# v1.net
KiCad netlist of a schematic drawn in Altium Designer
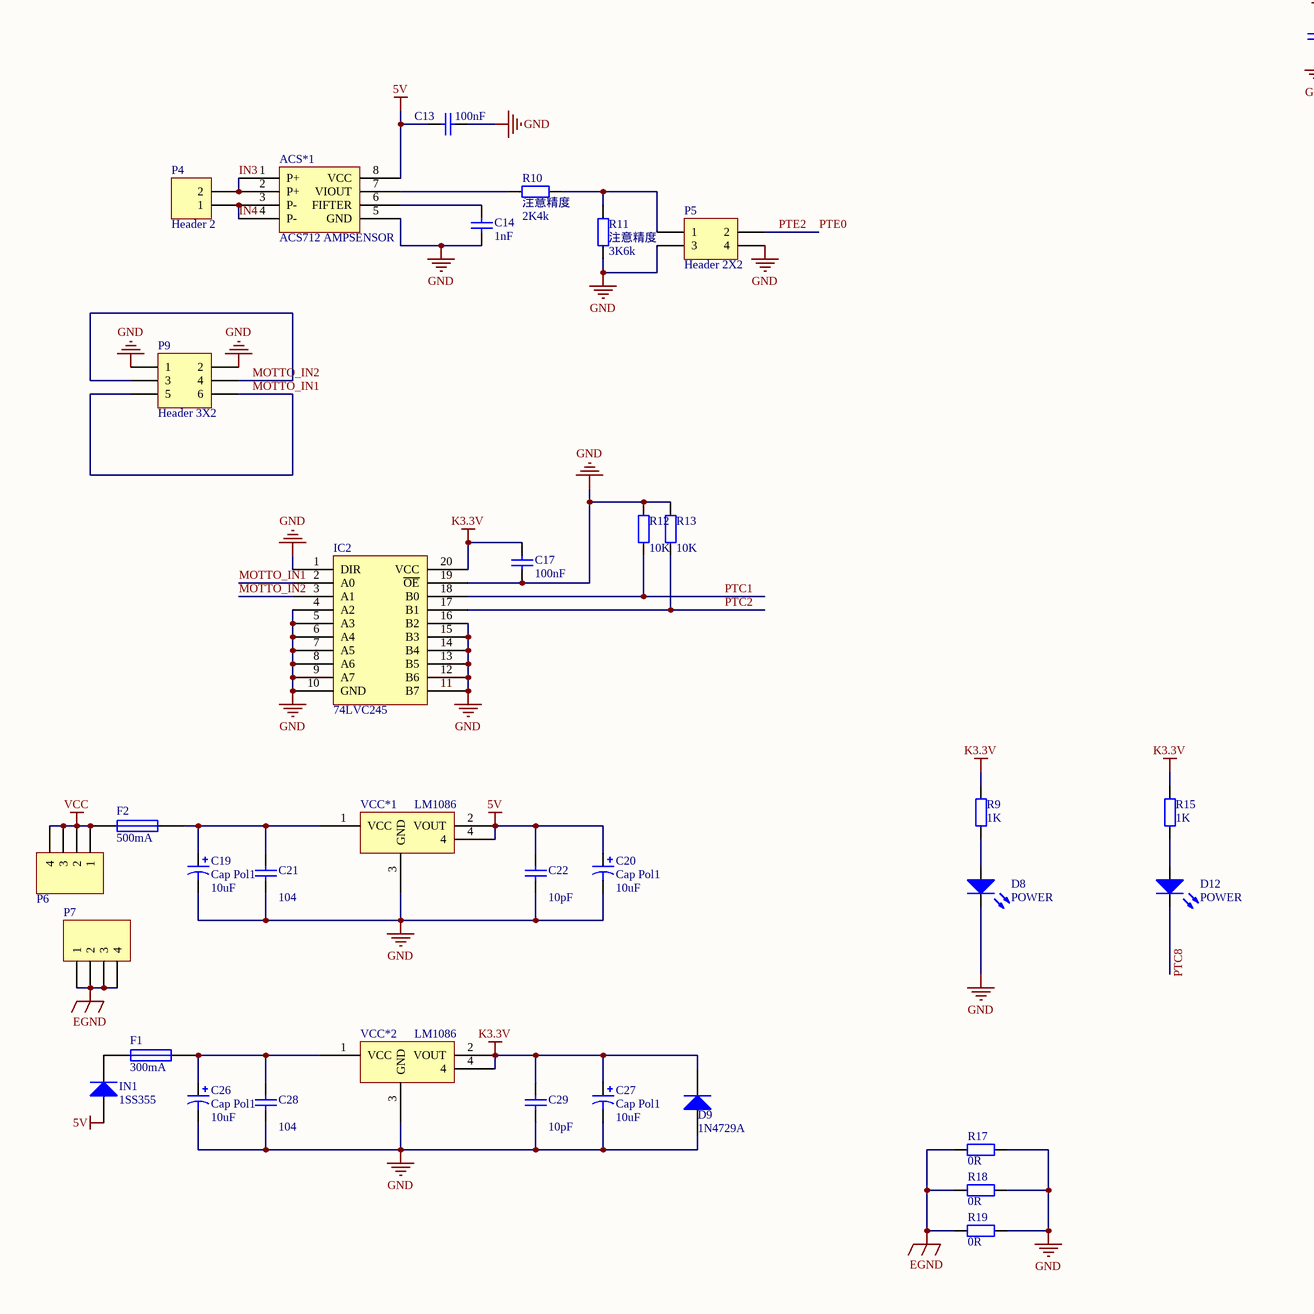
[diagram p0: 主控板加电流检测v1.SchDoc, left]
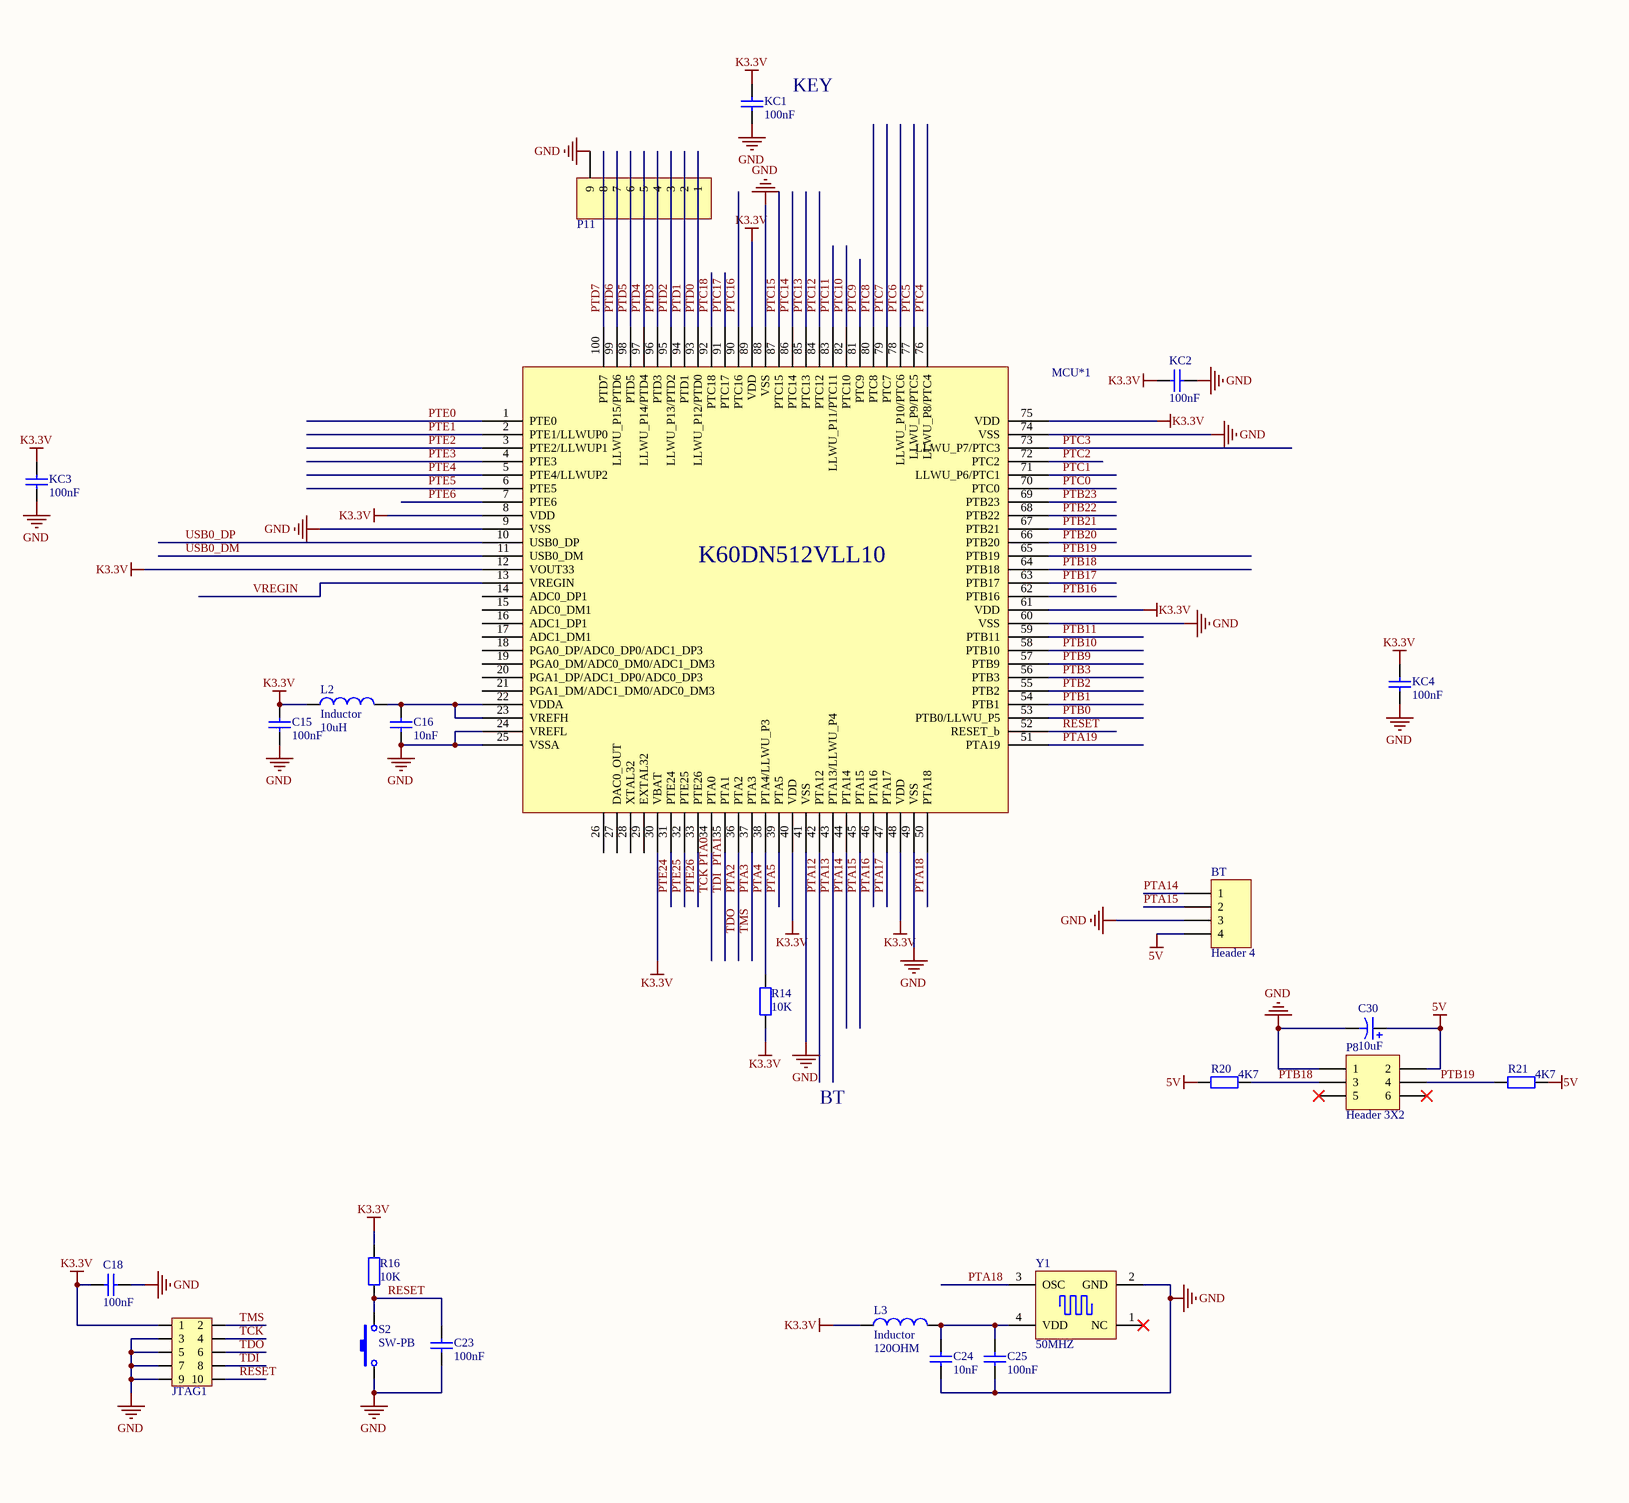
[diagram p1: 主控板加电流检测v1.SchDoc, right]

(export (version "E")
  (design (tool "Eeschema 10.0.6"))
  (components
    (comp (ref "ACS*1")
      (value "ACS712 AMPSENSOR")
      (footprint "SOIC1-8N ACS712")
      (libsource (lib "原理图") (part "ACS712 AMPSENSOR"))
    )
    (comp (ref "BT")
      (value "Header 4")
      (footprint "HDR1X4")
      (description "Header, 4-Pin")
      (fields (field (name "PUBLISHER") "Altium Limited"))
      (libsource (lib "") (part "Header 4_2"))
    )
    (comp (ref "C13")
      (value "100nF")
      (footprint "C2012")
      (description "Capacitor")
      (fields (field (name "Comment") "Cap") (field (name "PUBLISHER") "Altium Limited"))
      (libsource (lib "Miscellaneous Devices") (part "Cap"))
    )
    (comp (ref "C14")
      (value "1nF")
      (footprint "C2012")
      (description "Capacitor")
      (fields (field (name "Comment") "Cap") (field (name "PUBLISHER") "Altium Limited"))
      (libsource (lib "Miscellaneous Devices") (part "Cap"))
    )
    (comp (ref "C15")
      (value "100nF")
      (footprint "C2012")
      (description "Capacitor")
      (libsource (lib "K60-V4.0") (part "Cap"))
    )
    (comp (ref "C16")
      (value "10nF")
      (footprint "C2012")
      (description "Capacitor")
      (libsource (lib "K60-V4.0") (part "Cap"))
    )
    (comp (ref "C17")
      (value "100nF")
      (footprint "C2012")
      (description "Capacitor")
      (libsource (lib "Landzo") (part "Cap"))
    )
    (comp (ref "C18")
      (value "100nF")
      (footprint "C2012")
      (description "Capacitor")
      (libsource (lib "K60-V4.0") (part "Cap"))
    )
    (comp (ref "C19")
      (value "Cap Pol1")
      (footprint "1206(2)")
      (description "Polarized Capacitor (Radial)")
      (fields (field (name "ALTIUM_VALUE") "10uF") (field (name "PUBLISHER") "Altium Limited"))
      (libsource (lib "Miscellaneous Devices") (part "Cap Pol1"))
    )
    (comp (ref "C20")
      (value "Cap Pol1")
      (footprint "1206(2)")
      (description "Polarized Capacitor (Radial)")
      (fields (field (name "ALTIUM_VALUE") "10uF") (field (name "PUBLISHER") "Altium Limited"))
      (libsource (lib "Miscellaneous Devices") (part "Cap Pol1"))
    )
    (comp (ref "C21")
      (value "104")
      (footprint "C2012")
      (description "贴片电容")
      (fields (field (name "Comment") "Cap") (field (name "PUBLISHER") "Altium Limited"))
      (libsource (lib "Sparks") (part "Cap"))
    )
    (comp (ref "C22")
      (value "10pF")
      (footprint "C2012")
      (description "贴片电容")
      (fields (field (name "Comment") "Cap") (field (name "PUBLISHER") "Altium Limited"))
      (libsource (lib "Sparks") (part "Cap"))
    )
    (comp (ref "C23")
      (value "100nF")
      (footprint "C2012")
      (description "Capacitor")
      (libsource (lib "K60-V4.0") (part "Cap"))
    )
    (comp (ref "C24")
      (value "10nF")
      (footprint "C2012")
      (description "Capacitor")
      (libsource (lib "K60-V4.0") (part "Cap"))
    )
    (comp (ref "C25")
      (value "100nF")
      (footprint "C2012")
      (description "Capacitor")
      (libsource (lib "K60-V4.0") (part "Cap"))
    )
    (comp (ref "C26")
      (value "Cap Pol1")
      (footprint "1206(2)")
      (description "Polarized Capacitor (Radial)")
      (fields (field (name "ALTIUM_VALUE") "10uF") (field (name "PUBLISHER") "Altium Limited"))
      (libsource (lib "Miscellaneous Devices") (part "Cap Pol1"))
    )
    (comp (ref "C27")
      (value "Cap Pol1")
      (footprint "1206(2)")
      (description "Polarized Capacitor (Radial)")
      (fields (field (name "ALTIUM_VALUE") "10uF") (field (name "PUBLISHER") "Altium Limited"))
      (libsource (lib "Miscellaneous Devices") (part "Cap Pol1"))
    )
    (comp (ref "C28")
      (value "104")
      (footprint "C2012")
      (description "贴片电容")
      (fields (field (name "Comment") "Cap") (field (name "PUBLISHER") "Altium Limited"))
      (libsource (lib "Sparks") (part "Cap"))
    )
    (comp (ref "C29")
      (value "10pF")
      (footprint "C2012")
      (description "贴片电容")
      (fields (field (name "Comment") "Cap") (field (name "PUBLISHER") "Altium Limited"))
      (libsource (lib "Sparks") (part "Cap"))
    )
    (comp (ref "C30")
      (value "10uF")
      (footprint "c2012")
      (description "Polarized Capacitor (Radial)")
      (fields (field (name "Comment") "Cap Pol1") (field (name "PUBLISHER") "Altium Limited"))
      (libsource (lib "Miscellaneous Devices") (part "Cap Pol1"))
    )
    (comp (ref "D8")
      (value "POWER")
      (footprint "C2012")
      (description "Typical INFRARED GaAs LED")
      (libsource (lib "K60-V4.0") (part "LED"))
    )
    (comp (ref "D9")
      (value "1N4729A")
      (footprint "hole-chip diode")
      (description "High Conductance Fast Diode")
      (fields (field (name "PUBLISHER") "Altium Limited"))
      (libsource (lib "K60-V4.0") (part "Diode 1N4148"))
    )
    (comp (ref "D12")
      (value "POWER")
      (footprint "C2012")
      (description "Typical INFRARED GaAs LED")
      (libsource (lib "K60-V4.0") (part "LED"))
    )
    (comp (ref "F1")
      (value "300mA")
      (footprint "0805(2012)")
      (description "Fuse")
      (fields (field (name "PUBLISHER") "Altium Limited"))
      (libsource (lib "K60-V4.0") (part "Fuse 1"))
    )
    (comp (ref "F2")
      (value "500mA")
      (footprint "1206(2)")
      (description "Fuse")
      (fields (field (name "PUBLISHER") "Altium Limited"))
      (libsource (lib "K60-V4.0") (part "Fuse 1"))
    )
    (comp (ref "IC2")
      (value "74LVC245")
      (footprint "74LVC245 TSSOP")
      (libsource (lib "Landzo") (part "74LVC245"))
    )
    (comp (ref "IN1")
      (value "1SS355")
      (footprint "1206(2)")
      (description "High Conductance Fast Diode")
      (fields (field (name "PUBLISHER") "Altium Limited"))
      (libsource (lib "K60-V4.0") (part "Diode 1N4148"))
    )
    (comp (ref "JTAG1")
      (value "Header 5X2")
      (footprint "IDC5X2")
      (description "Header, 5-Pin, Dual row")
      (libsource (lib "K60-V4.0") (part "Header 5X2"))
    )
    (comp (ref "KC1")
      (value "100nF")
      (footprint "C2012")
      (description "Capacitor")
      (libsource (lib "K60-V4.0") (part "Cap"))
    )
    (comp (ref "KC2")
      (value "100nF")
      (footprint "C2012")
      (description "Capacitor")
      (libsource (lib "K60-V4.0") (part "Cap"))
    )
    (comp (ref "KC3")
      (value "100nF")
      (footprint "C2012")
      (description "Capacitor")
      (libsource (lib "K60-V4.0") (part "Cap"))
    )
    (comp (ref "KC4")
      (value "100nF")
      (footprint "C2012")
      (description "Capacitor")
      (libsource (lib "K60-V4.0") (part "Cap"))
    )
    (comp (ref "L2")
      (value "Inductor")
      (footprint "C2012")
      (fields (field (name "ALTIUM_VALUE") "10uH") (field (name "PUBLISHER") "Altium Limited"))
      (libsource (lib "Miscellaneous Devices") (part "Inductor"))
    )
    (comp (ref "L3")
      (value "Inductor")
      (footprint "C2012")
      (fields (field (name "ALTIUM_VALUE") "120OHM") (field (name "PUBLISHER") "Altium Limited"))
      (libsource (lib "Miscellaneous Devices") (part "Inductor"))
    )
    (comp (ref "MCU*1") (value "k60P100") (footprint "LQFP100") (libsource (lib "原理图") (part "k60P100")))
    (comp (ref "P4")
      (value "Header 2")
      (footprint "KF301-2P")
      (description "Header, 2-Pin")
      (fields (field (name "PUBLISHER") "Altium Limited"))
      (libsource (lib "Sparks") (part "Header 2"))
    )
    (comp (ref "P5")
      (value "Header 2X2")
      (footprint "HDR2X2")
      (description "Header, 2-Pin, Dual row")
      (fields (field (name "PUBLISHER") "Altium Limited"))
      (libsource (lib "Sparks") (part "Header 2X2"))
    )
    (comp (ref "P6")
      (value "Header 4")
      (footprint "HDR1X4")
      (description "Header, 4-Pin")
      (fields (field (name "PUBLISHER") "Altium Limited"))
      (libsource (lib "") (part "Header 4_1"))
    )
    (comp (ref "P7")
      (value "Header 4")
      (footprint "HDR1X4")
      (description "Header, 4-Pin")
      (fields (field (name "PUBLISHER") "Altium Limited"))
      (libsource (lib "Sparks") (part "Header 4"))
    )
    (comp (ref "P8")
      (value "Header 3X2")
      (footprint "HDR2X3")
      (description "Header, 3-Pin, Dual row")
      (fields (field (name "PUBLISHER") "Altium Limited"))
      (libsource (lib "Sparks") (part "Header 3X2"))
    )
    (comp (ref "P9")
      (value "Header 3X2")
      (footprint "HDR2X3")
      (description "Header, 3-Pin, Dual row")
      (fields (field (name "PUBLISHER") "Altium Limited"))
      (libsource (lib "Sparks") (part "Header 3X2"))
    )
    (comp (ref "P11")
      (value "Header 9")
      (footprint "FFC/SM1.0-2H9")
      (description "Header, 9-Pin")
      (fields (field (name "PUBLISHER") "Altium Limited"))
      (libsource (lib "Miscellaneous Connectors") (part "Header 9"))
    )
    (comp (ref "R9")
      (value "1K")
      (footprint "R2012")
      (description "Resistor of led")
      (libsource (lib "K60-V4.0") (part "Res"))
    )
    (comp (ref "R10")
      (value "注意精度")
      (footprint "R2012")
      (description "Resistor")
      (fields (field (name "ALTIUM_VALUE") "2K4k") (field (name "PUBLISHER") "Altium Limited"))
      (libsource (lib "") (part "Res2_2"))
    )
    (comp (ref "R11")
      (value "注意精度")
      (footprint "R2012")
      (description "Resistor")
      (fields (field (name "ALTIUM_VALUE") "3K6k") (field (name "PUBLISHER") "Altium Limited"))
      (libsource (lib "Miscellaneous Devices") (part "Res2"))
    )
    (comp (ref "R12")
      (value "10K")
      (footprint "R2012")
      (description "Resistor")
      (fields (field (name "Comment") "Res2") (field (name "PUBLISHER") "Altium Limited"))
      (libsource (lib "Miscellaneous Devices") (part "Res2"))
    )
    (comp (ref "R13")
      (value "10K")
      (footprint "R2012")
      (description "Resistor")
      (fields (field (name "Comment") "Res2") (field (name "PUBLISHER") "Altium Limited"))
      (libsource (lib "Miscellaneous Devices") (part "Res2"))
    )
    (comp (ref "R14")
      (value "10K")
      (footprint "R2012")
      (description "Resistor of led")
      (libsource (lib "K60-V4.0") (part "Res"))
    )
    (comp (ref "R15")
      (value "1K")
      (footprint "R2012")
      (description "Resistor of led")
      (libsource (lib "K60-V4.0") (part "Res"))
    )
    (comp (ref "R16")
      (value "10K")
      (footprint "R2012")
      (description "Resistor")
      (libsource (lib "K60-V4.0") (part "Res"))
    )
    (comp (ref "R17")
      (value "0R")
      (footprint "1206(2)")
      (description "Resistor")
      (fields (field (name "Comment") "Res2") (field (name "PUBLISHER") "Altium Limited"))
      (libsource (lib "landzo_mos") (part "Res2"))
    )
    (comp (ref "R18")
      (value "0R")
      (footprint "1206(2)")
      (description "Resistor")
      (fields (field (name "Comment") "Res2") (field (name "PUBLISHER") "Altium Limited"))
      (libsource (lib "landzo_mos") (part "Res2"))
    )
    (comp (ref "R19")
      (value "0R")
      (footprint "1206(2)")
      (description "Resistor")
      (fields (field (name "Comment") "Res2") (field (name "PUBLISHER") "Altium Limited"))
      (libsource (lib "landzo_mos") (part "Res2"))
    )
    (comp (ref "R20")
      (value "4K7")
      (footprint "R2012")
      (description "Resistor")
      (fields (field (name "Comment") "Res2") (field (name "PUBLISHER") "Altium Limited"))
      (libsource (lib "") (part "Res2_1"))
    )
    (comp (ref "R21")
      (value "4K7")
      (footprint "R2012")
      (description "Resistor")
      (fields (field (name "Comment") "Res2") (field (name "PUBLISHER") "Altium Limited"))
      (libsource (lib "") (part "Res2_1"))
    )
    (comp (ref "S2")
      (value "SW-PB")
      (footprint "sw 3*4 *2")
      (description "Switch")
      (libsource (lib "K60-V4.0") (part "SW-PB"))
    )
    (comp (ref "VCC*1") (value "LM1086") (footprint "DPAK LM2940") (libsource (lib "2号库") (part "LM1086")))
    (comp (ref "VCC*2") (value "LM1086") (footprint "lm1117") (libsource (lib "2号库") (part "LM1086")))
    (comp (ref "Y1") (value "50MHZ") (footprint "贴片有源晶体") (libsource (lib "K60-V4.0") (part "XTAL1")))
  )
  (nets
    (net (code "1") (name "/IN3") (class "Default")
      (node (ref "ACS*1") (pin "1") (pinfunction "P+_1") (pintype "passive"))
      (node (ref "ACS*1") (pin "2") (pinfunction "P+_2") (pintype "passive"))
      (node (ref "P4") (pin "2") (pinfunction "2_2") (pintype "passive"))
    )
    (net (code "2") (name "/IN4") (class "Default")
      (node (ref "ACS*1") (pin "3") (pinfunction "P-_3") (pintype "passive"))
      (node (ref "ACS*1") (pin "4") (pinfunction "P-_4") (pintype "passive"))
      (node (ref "P4") (pin "1") (pinfunction "1_1") (pintype "passive"))
    )
    (net (code "3") (name "/MOTTO_IN1") (class "Default")
      (node (ref "IC2") (pin "2") (pinfunction "A0_2") (pintype "passive"))
      (node (ref "P9") (pin "5") (pinfunction "5_5") (pintype "passive"))
      (node (ref "P9") (pin "6") (pinfunction "6_6") (pintype "passive"))
    )
    (net (code "4") (name "/MOTTO_IN2") (class "Default")
      (node (ref "IC2") (pin "3") (pinfunction "A1_3") (pintype "passive"))
      (node (ref "P9") (pin "3") (pinfunction "3_3") (pintype "passive"))
      (node (ref "P9") (pin "4") (pinfunction "4_4") (pintype "passive"))
    )
    (net (code "5") (name "/PTA0") (class "Default")
      (node (ref "JTAG1") (pin "4") (pinfunction "4_4") (pintype "passive"))
      (node (ref "MCU*1") (pin "34") (pinfunction "PTA0_34") (pintype "passive"))
    )
    (net (code "6") (name "/PTA1") (class "Default")
      (node (ref "JTAG1") (pin "8") (pinfunction "8_8") (pintype "passive"))
      (node (ref "MCU*1") (pin "35") (pinfunction "PTA1_35") (pintype "passive"))
    )
    (net (code "7") (name "/PTA2") (class "Default")
      (node (ref "JTAG1") (pin "6") (pinfunction "6_6") (pintype "passive"))
      (node (ref "MCU*1") (pin "36") (pinfunction "PTA2_36") (pintype "passive"))
    )
    (net (code "8") (name "/PTA3") (class "Default")
      (node (ref "JTAG1") (pin "2") (pinfunction "2_2") (pintype "passive"))
      (node (ref "MCU*1") (pin "37") (pinfunction "PTA3_37") (pintype "passive"))
    )
    (net (code "9") (name "/PTA4") (class "Default")
      (node (ref "MCU*1") (pin "38") (pinfunction "PTA4/LLWU_P3_38") (pintype "passive"))
      (node (ref "R14") (pin "2") (pinfunction "2_2") (pintype "passive"))
    )
    (net (code "10") (name "/PTA5") (class "Default")
      (node (ref "MCU*1") (pin "39") (pinfunction "PTA5_39") (pintype "passive"))
    )
    (net (code "11") (name "/PTA12") (class "Default")
      (node (ref "MCU*1") (pin "42") (pinfunction "PTA12_42") (pintype "passive"))
    )
    (net (code "12") (name "/PTA13") (class "Default")
      (node (ref "MCU*1") (pin "43") (pinfunction "PTA13/LLWU_P4_43") (pintype "passive"))
    )
    (net (code "13") (name "/PTA14") (class "Default")
      (node (ref "BT") (pin "1") (pinfunction "1_1") (pintype "passive"))
      (node (ref "MCU*1") (pin "44") (pinfunction "PTA14_44") (pintype "passive"))
    )
    (net (code "14") (name "/PTA15") (class "Default")
      (node (ref "BT") (pin "2") (pinfunction "2_2") (pintype "passive"))
      (node (ref "MCU*1") (pin "45") (pinfunction "PTA15_45") (pintype "passive"))
    )
    (net (code "15") (name "/PTA16") (class "Default")
      (node (ref "MCU*1") (pin "46") (pinfunction "PTA16_46") (pintype "passive"))
    )
    (net (code "16") (name "/PTA17") (class "Default")
      (node (ref "MCU*1") (pin "47") (pinfunction "PTA17_47") (pintype "passive"))
    )
    (net (code "17") (name "/PTA18") (class "Default")
      (node (ref "MCU*1") (pin "50") (pinfunction "PTA18_50") (pintype "passive"))
      (node (ref "Y1") (pin "3") (pinfunction "OSC_3") (pintype "passive"))
    )
    (net (code "18") (name "/PTA19") (class "Default")
      (node (ref "MCU*1") (pin "51") (pinfunction "PTA19_51") (pintype "passive"))
    )
    (net (code "19") (name "/PTB0") (class "Default")
      (node (ref "MCU*1") (pin "53") (pinfunction "PTB0/LLWU_P5_53") (pintype "passive"))
    )
    (net (code "20") (name "/PTB1") (class "Default")
      (node (ref "MCU*1") (pin "54") (pinfunction "PTB1_54") (pintype "passive"))
    )
    (net (code "21") (name "/PTB2") (class "Default")
      (node (ref "MCU*1") (pin "55") (pinfunction "PTB2_55") (pintype "passive"))
    )
    (net (code "22") (name "/PTB3") (class "Default")
      (node (ref "MCU*1") (pin "56") (pinfunction "PTB3_56") (pintype "passive"))
    )
    (net (code "23") (name "/PTB9") (class "Default")
      (node (ref "MCU*1") (pin "57") (pinfunction "PTB9_57") (pintype "passive"))
    )
    (net (code "24") (name "/PTB10") (class "Default")
      (node (ref "MCU*1") (pin "58") (pinfunction "PTB10_58") (pintype "passive"))
    )
    (net (code "25") (name "/PTB11") (class "Default")
      (node (ref "MCU*1") (pin "59") (pinfunction "PTB11_59") (pintype "passive"))
    )
    (net (code "26") (name "/PTB16") (class "Default")
      (node (ref "MCU*1") (pin "62") (pinfunction "PTB16_62") (pintype "passive"))
    )
    (net (code "27") (name "/PTB17") (class "Default")
      (node (ref "MCU*1") (pin "63") (pinfunction "PTB17_63") (pintype "passive"))
    )
    (net (code "28") (name "/PTB18") (class "Default")
      (node (ref "MCU*1") (pin "64") (pinfunction "PTB18_64") (pintype "passive"))
      (node (ref "P8") (pin "3") (pinfunction "3_3") (pintype "passive"))
      (node (ref "R20") (pin "1") (pinfunction "1_1") (pintype "passive"))
    )
    (net (code "29") (name "/PTB19") (class "Default")
      (node (ref "MCU*1") (pin "65") (pinfunction "PTB19_65") (pintype "passive"))
      (node (ref "P8") (pin "4") (pinfunction "4_4") (pintype "passive"))
      (node (ref "R21") (pin "2") (pinfunction "2_2") (pintype "passive"))
    )
    (net (code "30") (name "/PTB20") (class "Default")
      (node (ref "MCU*1") (pin "66") (pinfunction "PTB20_66") (pintype "passive"))
    )
    (net (code "31") (name "/PTB21") (class "Default")
      (node (ref "MCU*1") (pin "67") (pinfunction "PTB21_67") (pintype "passive"))
    )
    (net (code "32") (name "/PTB22") (class "Default")
      (node (ref "MCU*1") (pin "68") (pinfunction "PTB22_68") (pintype "passive"))
    )
    (net (code "33") (name "/PTB23") (class "Default")
      (node (ref "MCU*1") (pin "69") (pinfunction "PTB23_69") (pintype "passive"))
    )
    (net (code "34") (name "/PTC0") (class "Default")
      (node (ref "MCU*1") (pin "70") (pinfunction "PTC0_70") (pintype "passive"))
    )
    (net (code "35") (name "/PTC1") (class "Default")
      (node (ref "IC2") (pin "18") (pinfunction "B0_18") (pintype "passive"))
      (node (ref "MCU*1") (pin "71") (pinfunction "LLWU_P6/PTC1_71") (pintype "passive"))
      (node (ref "R12") (pin "1") (pinfunction "1_1") (pintype "passive"))
    )
    (net (code "36") (name "/PTC2") (class "Default")
      (node (ref "IC2") (pin "17") (pinfunction "B1_17") (pintype "passive"))
      (node (ref "MCU*1") (pin "72") (pinfunction "PTC2_72") (pintype "passive"))
      (node (ref "R13") (pin "1") (pinfunction "1_1") (pintype "passive"))
    )
    (net (code "37") (name "/PTC3") (class "Default")
      (node (ref "MCU*1") (pin "73") (pinfunction "LLWU_P7/PTC3_73") (pintype "passive"))
    )
    (net (code "38") (name "/PTC4") (class "Default")
      (node (ref "MCU*1") (pin "76") (pinfunction "LLWU_P8/PTC4_76") (pintype "passive"))
    )
    (net (code "39") (name "/PTC5") (class "Default")
      (node (ref "MCU*1") (pin "77") (pinfunction "LLWU_P9/PTC5_77") (pintype "passive"))
    )
    (net (code "40") (name "/PTC6") (class "Default")
      (node (ref "MCU*1") (pin "78") (pinfunction "LLWU_P10/PTC6_78") (pintype "passive"))
    )
    (net (code "41") (name "/PTC7") (class "Default")
      (node (ref "MCU*1") (pin "79") (pinfunction "PTC7_79") (pintype "passive"))
    )
    (net (code "42") (name "/PTC8") (class "Default")
      (node (ref "D12") (pin "2") (pinfunction "2_2") (pintype "passive"))
      (node (ref "MCU*1") (pin "80") (pinfunction "PTC8_80") (pintype "passive"))
    )
    (net (code "43") (name "/PTC9") (class "Default")
      (node (ref "MCU*1") (pin "81") (pinfunction "PTC9_81") (pintype "passive"))
    )
    (net (code "44") (name "/PTC10") (class "Default")
      (node (ref "MCU*1") (pin "82") (pinfunction "PTC10_82") (pintype "passive"))
    )
    (net (code "45") (name "/PTC11") (class "Default")
      (node (ref "MCU*1") (pin "83") (pinfunction "LLWU_P11/PTC11_83") (pintype "passive"))
    )
    (net (code "46") (name "/PTC12") (class "Default")
      (node (ref "MCU*1") (pin "84") (pinfunction "PTC12_84") (pintype "passive"))
    )
    (net (code "47") (name "/PTC13") (class "Default")
      (node (ref "MCU*1") (pin "85") (pinfunction "PTC13_85") (pintype "passive"))
    )
    (net (code "48") (name "/PTC14") (class "Default")
      (node (ref "MCU*1") (pin "86") (pinfunction "PTC14_86") (pintype "passive"))
    )
    (net (code "49") (name "/PTC15") (class "Default")
      (node (ref "MCU*1") (pin "87") (pinfunction "PTC15_87") (pintype "passive"))
    )
    (net (code "50") (name "/PTC16") (class "Default")
      (node (ref "MCU*1") (pin "90") (pinfunction "PTC16_90") (pintype "passive"))
    )
    (net (code "51") (name "/PTC17") (class "Default")
      (node (ref "MCU*1") (pin "91") (pinfunction "PTC17_91") (pintype "passive"))
    )
    (net (code "52") (name "/PTC18") (class "Default")
      (node (ref "MCU*1") (pin "92") (pinfunction "PTC18_92") (pintype "passive"))
    )
    (net (code "53") (name "/PTD0") (class "Default")
      (node (ref "MCU*1") (pin "93") (pinfunction "LLWU_P12/PTD0_93") (pintype "passive"))
      (node (ref "P11") (pin "1") (pinfunction "1_1") (pintype "passive"))
    )
    (net (code "54") (name "/PTD1") (class "Default")
      (node (ref "MCU*1") (pin "94") (pinfunction "PTD1_94") (pintype "passive"))
      (node (ref "P11") (pin "2") (pinfunction "2_2") (pintype "passive"))
    )
    (net (code "55") (name "/PTD2") (class "Default")
      (node (ref "MCU*1") (pin "95") (pinfunction "LLWU_P13/PTD2_95") (pintype "passive"))
      (node (ref "P11") (pin "3") (pinfunction "3_3") (pintype "passive"))
    )
    (net (code "56") (name "/PTD3") (class "Default")
      (node (ref "MCU*1") (pin "96") (pinfunction "PTD3_96") (pintype "passive"))
      (node (ref "P11") (pin "4") (pinfunction "4_4") (pintype "passive"))
    )
    (net (code "57") (name "/PTD4") (class "Default")
      (node (ref "MCU*1") (pin "97") (pinfunction "LLWU_P14/PTD4_97") (pintype "passive"))
      (node (ref "P11") (pin "5") (pinfunction "5_5") (pintype "passive"))
    )
    (net (code "58") (name "/PTD5") (class "Default")
      (node (ref "MCU*1") (pin "98") (pinfunction "PTD5_98") (pintype "passive"))
      (node (ref "P11") (pin "6") (pinfunction "6_6") (pintype "passive"))
    )
    (net (code "59") (name "/PTD6") (class "Default")
      (node (ref "MCU*1") (pin "99") (pinfunction "LLWU_P15/PTD6_99") (pintype "passive"))
      (node (ref "P11") (pin "7") (pinfunction "7_7") (pintype "passive"))
    )
    (net (code "60") (name "/PTD7") (class "Default")
      (node (ref "MCU*1") (pin "100") (pinfunction "PTD7_100") (pintype "passive"))
      (node (ref "P11") (pin "8") (pinfunction "8_8") (pintype "passive"))
    )
    (net (code "61") (name "/PTE0") (class "Default")
      (node (ref "MCU*1") (pin "1") (pinfunction "PTE0_1") (pintype "passive"))
      (node (ref "MCU*1") (pin "3") (pinfunction "PTE2/LLWUP1_3") (pintype "passive"))
      (node (ref "P5") (pin "2") (pinfunction "2_2") (pintype "passive"))
    )
    (net (code "62") (name "/PTE1") (class "Default")
      (node (ref "MCU*1") (pin "2") (pinfunction "PTE1/LLWUP0_2") (pintype "passive"))
    )
    (net (code "63") (name "/PTE3") (class "Default")
      (node (ref "MCU*1") (pin "4") (pinfunction "PTE3_4") (pintype "passive"))
    )
    (net (code "64") (name "/PTE4") (class "Default")
      (node (ref "MCU*1") (pin "5") (pinfunction "PTE4/LLWUP2_5") (pintype "passive"))
    )
    (net (code "65") (name "/PTE5") (class "Default")
      (node (ref "MCU*1") (pin "6") (pinfunction "PTE5_6") (pintype "passive"))
    )
    (net (code "66") (name "/PTE6") (class "Default")
      (node (ref "MCU*1") (pin "7") (pinfunction "PTE6_7") (pintype "passive"))
    )
    (net (code "67") (name "/PTE24") (class "Default")
      (node (ref "MCU*1") (pin "31") (pinfunction "PTE24_31") (pintype "passive"))
    )
    (net (code "68") (name "/PTE25") (class "Default")
      (node (ref "MCU*1") (pin "32") (pinfunction "PTE25_32") (pintype "passive"))
    )
    (net (code "69") (name "/PTE26") (class "Default")
      (node (ref "MCU*1") (pin "33") (pinfunction "PTE26_33") (pintype "passive"))
    )
    (net (code "70") (name "/RESET") (class "Default")
      (node (ref "C23") (pin "2") (pinfunction "2_2") (pintype "passive"))
      (node (ref "JTAG1") (pin "10") (pinfunction "10_10") (pintype "passive"))
      (node (ref "MCU*1") (pin "52") (pinfunction "RESET_b_52") (pintype "passive"))
      (node (ref "R16") (pin "1") (pinfunction "1_1") (pintype "passive"))
      (node (ref "S2") (pin "2") (pinfunction "2_2") (pintype "passive"))
    )
    (net (code "71") (name "/USB0_DM") (class "Default")
      (node (ref "MCU*1") (pin "11") (pinfunction "USB0_DM_11") (pintype "passive"))
    )
    (net (code "72") (name "/USB0_DP") (class "Default")
      (node (ref "MCU*1") (pin "10") (pinfunction "USB0_DP_10") (pintype "passive"))
    )
    (net (code "73") (name "/VREGIN") (class "Default")
      (node (ref "MCU*1") (pin "13") (pinfunction "VREGIN_13") (pintype "passive"))
    )
    (net (code "74") (name "5V") (class "Default")
      (node (ref "ACS*1") (pin "8") (pinfunction "VCC_8") (pintype "passive"))
      (node (ref "BT") (pin "4") (pinfunction "4_4") (pintype "passive"))
      (node (ref "C13") (pin "2") (pinfunction "2_2") (pintype "passive"))
      (node (ref "C20") (pin "1") (pinfunction "1_1") (pintype "passive"))
      (node (ref "C22") (pin "2") (pinfunction "2_2") (pintype "passive"))
      (node (ref "C30") (pin "1") (pinfunction "1_1") (pintype "passive"))
      (node (ref "IN1") (pin "1") (pinfunction "A_1") (pintype "passive"))
      (node (ref "P8") (pin "2") (pinfunction "2_2") (pintype "passive"))
      (node (ref "R20") (pin "2") (pinfunction "2_2") (pintype "passive"))
      (node (ref "R21") (pin "1") (pinfunction "1_1") (pintype "passive"))
      (node (ref "VCC*1") (pin "2") (pinfunction "VOUT_2") (pintype "passive"))
      (node (ref "VCC*1") (pin "4") (pinfunction "4_4") (pintype "passive"))
    )
    (net (code "75") (name "EGND") (class "Default")
      (node (ref "P7") (pin "1") (pinfunction "1_1") (pintype "passive"))
      (node (ref "P7") (pin "2") (pinfunction "2_2") (pintype "passive"))
      (node (ref "P7") (pin "3") (pinfunction "3_3") (pintype "passive"))
      (node (ref "P7") (pin "4") (pinfunction "4_4") (pintype "passive"))
      (node (ref "R17") (pin "1") (pinfunction "1_1") (pintype "passive"))
      (node (ref "R18") (pin "1") (pinfunction "1_1") (pintype "passive"))
      (node (ref "R19") (pin "1") (pinfunction "1_1") (pintype "passive"))
    )
    (net (code "76") (name "GND") (class "Default")
      (node (ref "ACS*1") (pin "5") (pinfunction "GND_5") (pintype "passive"))
      (node (ref "BT") (pin "3") (pinfunction "3_3") (pintype "passive"))
      (node (ref "C13") (pin "1") (pinfunction "1_1") (pintype "passive"))
      (node (ref "C14") (pin "2") (pinfunction "2_2") (pintype "passive"))
      (node (ref "C15") (pin "1") (pinfunction "1_1") (pintype "passive"))
      (node (ref "C16") (pin "1") (pinfunction "1_1") (pintype "passive"))
      (node (ref "C17") (pin "2") (pinfunction "2_2") (pintype "passive"))
      (node (ref "C18") (pin "2") (pinfunction "2_2") (pintype "passive"))
      (node (ref "C19") (pin "2") (pinfunction "2_2") (pintype "passive"))
      (node (ref "C20") (pin "2") (pinfunction "2_2") (pintype "passive"))
      (node (ref "C21") (pin "1") (pinfunction "1_1") (pintype "passive"))
      (node (ref "C22") (pin "1") (pinfunction "1_1") (pintype "passive"))
      (node (ref "C23") (pin "1") (pinfunction "1_1") (pintype "passive"))
      (node (ref "C24") (pin "1") (pinfunction "1_1") (pintype "passive"))
      (node (ref "C25") (pin "1") (pinfunction "1_1") (pintype "passive"))
      (node (ref "C26") (pin "2") (pinfunction "2_2") (pintype "passive"))
      (node (ref "C27") (pin "2") (pinfunction "2_2") (pintype "passive"))
      (node (ref "C28") (pin "1") (pinfunction "1_1") (pintype "passive"))
      (node (ref "C29") (pin "1") (pinfunction "1_1") (pintype "passive"))
      (node (ref "C30") (pin "2") (pinfunction "2_2") (pintype "passive"))
      (node (ref "D8") (pin "2") (pinfunction "2_2") (pintype "passive"))
      (node (ref "D9") (pin "1") (pinfunction "A_1") (pintype "passive"))
      (node (ref "IC2") (pin "1") (pinfunction "DIR_1") (pintype "passive"))
      (node (ref "IC2") (pin "10") (pinfunction "GND_10") (pintype "passive"))
      (node (ref "IC2") (pin "11") (pinfunction "B7_11") (pintype "passive"))
      (node (ref "IC2") (pin "12") (pinfunction "B6_12") (pintype "passive"))
      (node (ref "IC2") (pin "13") (pinfunction "B5_13") (pintype "passive"))
      (node (ref "IC2") (pin "14") (pinfunction "B4_14") (pintype "passive"))
      (node (ref "IC2") (pin "15") (pinfunction "B3_15") (pintype "passive"))
      (node (ref "IC2") (pin "16") (pinfunction "B2_16") (pintype "passive"))
      (node (ref "IC2") (pin "19") (pinfunction "~{OE}_19") (pintype "passive"))
      (node (ref "IC2") (pin "4") (pinfunction "A2_4") (pintype "passive"))
      (node (ref "IC2") (pin "5") (pinfunction "A3_5") (pintype "passive"))
      (node (ref "IC2") (pin "6") (pinfunction "A4_6") (pintype "passive"))
      (node (ref "IC2") (pin "7") (pinfunction "A5_7") (pintype "passive"))
      (node (ref "IC2") (pin "8") (pinfunction "A6_8") (pintype "passive"))
      (node (ref "IC2") (pin "9") (pinfunction "A7_9") (pintype "passive"))
      (node (ref "JTAG1") (pin "3") (pinfunction "3_3") (pintype "passive"))
      (node (ref "JTAG1") (pin "5") (pinfunction "5_5") (pintype "passive"))
      (node (ref "JTAG1") (pin "7") (pinfunction "7_7") (pintype "passive"))
      (node (ref "JTAG1") (pin "9") (pinfunction "9_9") (pintype "passive"))
      (node (ref "KC1") (pin "1") (pinfunction "1_1") (pintype "passive"))
      (node (ref "KC2") (pin "1") (pinfunction "1_1") (pintype "passive"))
      (node (ref "KC3") (pin "1") (pinfunction "1_1") (pintype "passive"))
      (node (ref "KC4") (pin "1") (pinfunction "1_1") (pintype "passive"))
      (node (ref "MCU*1") (pin "24") (pinfunction "VREFL_24") (pintype "passive"))
      (node (ref "MCU*1") (pin "25") (pinfunction "VSSA_25") (pintype "passive"))
      (node (ref "MCU*1") (pin "41") (pinfunction "VSS_41") (pintype "passive"))
      (node (ref "MCU*1") (pin "49") (pinfunction "VSS_49") (pintype "passive"))
      (node (ref "MCU*1") (pin "60") (pinfunction "VSS_60") (pintype "passive"))
      (node (ref "MCU*1") (pin "74") (pinfunction "VSS_74") (pintype "passive"))
      (node (ref "MCU*1") (pin "88") (pinfunction "VSS_88") (pintype "passive"))
      (node (ref "MCU*1") (pin "9") (pinfunction "VSS_9") (pintype "passive"))
      (node (ref "P11") (pin "9") (pinfunction "9_9") (pintype "passive"))
      (node (ref "P5") (pin "3") (pinfunction "3_3") (pintype "passive"))
      (node (ref "P5") (pin "4") (pinfunction "4_4") (pintype "passive"))
      (node (ref "P8") (pin "1") (pinfunction "1_1") (pintype "passive"))
      (node (ref "P9") (pin "1") (pinfunction "1_1") (pintype "passive"))
      (node (ref "P9") (pin "2") (pinfunction "2_2") (pintype "passive"))
      (node (ref "R11") (pin "1") (pinfunction "1_1") (pintype "passive"))
      (node (ref "R12") (pin "2") (pinfunction "2_2") (pintype "passive"))
      (node (ref "R13") (pin "2") (pinfunction "2_2") (pintype "passive"))
      (node (ref "R17") (pin "2") (pinfunction "2_2") (pintype "passive"))
      (node (ref "R18") (pin "2") (pinfunction "2_2") (pintype "passive"))
      (node (ref "R19") (pin "2") (pinfunction "2_2") (pintype "passive"))
      (node (ref "S2") (pin "1") (pinfunction "1_1") (pintype "passive"))
      (node (ref "VCC*1") (pin "3") (pinfunction "GND_3") (pintype "passive"))
      (node (ref "VCC*2") (pin "3") (pinfunction "GND_3") (pintype "passive"))
      (node (ref "Y1") (pin "2") (pinfunction "GND_2") (pintype "passive"))
    )
    (net (code "77") (name "K3.3V") (class "Default")
      (node (ref "C15") (pin "2") (pinfunction "2_2") (pintype "passive"))
      (node (ref "C17") (pin "1") (pinfunction "1_1") (pintype "passive"))
      (node (ref "C18") (pin "1") (pinfunction "1_1") (pintype "passive"))
      (node (ref "C27") (pin "1") (pinfunction "1_1") (pintype "passive"))
      (node (ref "C29") (pin "2") (pinfunction "2_2") (pintype "passive"))
      (node (ref "D9") (pin "2") (pinfunction "K_2") (pintype "passive"))
      (node (ref "IC2") (pin "20") (pinfunction "VCC_20") (pintype "passive"))
      (node (ref "JTAG1") (pin "1") (pinfunction "1_1") (pintype "passive"))
      (node (ref "KC1") (pin "2") (pinfunction "2_2") (pintype "passive"))
      (node (ref "KC2") (pin "2") (pinfunction "2_2") (pintype "passive"))
      (node (ref "KC3") (pin "2") (pinfunction "2_2") (pintype "passive"))
      (node (ref "KC4") (pin "2") (pinfunction "2_2") (pintype "passive"))
      (node (ref "L2") (pin "1") (pinfunction "1_1") (pintype "passive"))
      (node (ref "L3") (pin "1") (pinfunction "1_1") (pintype "passive"))
      (node (ref "MCU*1") (pin "12") (pinfunction "VOUT33_12") (pintype "passive"))
      (node (ref "MCU*1") (pin "30") (pinfunction "VBAT_30") (pintype "passive"))
      (node (ref "MCU*1") (pin "40") (pinfunction "VDD_40") (pintype "passive"))
      (node (ref "MCU*1") (pin "48") (pinfunction "VDD_48") (pintype "passive"))
      (node (ref "MCU*1") (pin "61") (pinfunction "VDD_61") (pintype "passive"))
      (node (ref "MCU*1") (pin "75") (pinfunction "VDD_75") (pintype "passive"))
      (node (ref "MCU*1") (pin "8") (pinfunction "VDD_8") (pintype "passive"))
      (node (ref "MCU*1") (pin "89") (pinfunction "VDD_89") (pintype "passive"))
      (node (ref "R14") (pin "1") (pinfunction "1_1") (pintype "passive"))
      (node (ref "R15") (pin "2") (pinfunction "2_2") (pintype "passive"))
      (node (ref "R16") (pin "2") (pinfunction "2_2") (pintype "passive"))
      (node (ref "R9") (pin "2") (pinfunction "2_2") (pintype "passive"))
      (node (ref "VCC*2") (pin "2") (pinfunction "VOUT_2") (pintype "passive"))
      (node (ref "VCC*2") (pin "4") (pinfunction "4_4") (pintype "passive"))
    )
    (net (code "78") (name "Net-(ACS*1-FIFTER)") (class "Default")
      (node (ref "ACS*1") (pin "6") (pinfunction "FIFTER_6") (pintype "passive"))
      (node (ref "C14") (pin "1") (pinfunction "1_1") (pintype "passive"))
    )
    (net (code "79") (name "Net-(ACS*1-VIOUT)") (class "Default")
      (node (ref "ACS*1") (pin "7") (pinfunction "VIOUT_7") (pintype "passive"))
      (node (ref "R10") (pin "1") (pinfunction "1_1") (pintype "passive"))
    )
    (net (code "80") (name "Net-(D8-Pad1)") (class "Default")
      (node (ref "D8") (pin "1") (pinfunction "1_1") (pintype "passive"))
      (node (ref "R9") (pin "1") (pinfunction "1_1") (pintype "passive"))
    )
    (net (code "81") (name "Net-(D12-Pad1)") (class "Default")
      (node (ref "D12") (pin "1") (pinfunction "1_1") (pintype "passive"))
      (node (ref "R15") (pin "1") (pinfunction "1_1") (pintype "passive"))
    )
    (net (code "82") (name "Net-(IN1-K)") (class "Default")
      (node (ref "F1") (pin "2") (pinfunction "2_2") (pintype "passive"))
      (node (ref "IN1") (pin "2") (pinfunction "K_2") (pintype "passive"))
    )
    (net (code "83") (name "Net-(MCU*1-VDDA)") (class "Default")
      (node (ref "C16") (pin "2") (pinfunction "2_2") (pintype "passive"))
      (node (ref "L2") (pin "2") (pinfunction "2_2") (pintype "passive"))
      (node (ref "MCU*1") (pin "22") (pinfunction "VDDA_22") (pintype "passive"))
      (node (ref "MCU*1") (pin "23") (pinfunction "VREFH_23") (pintype "passive"))
    )
    (net (code "84") (name "Net-(P5-Pad1)") (class "Default")
      (node (ref "P5") (pin "1") (pinfunction "1_1") (pintype "passive"))
      (node (ref "R10") (pin "2") (pinfunction "2_2") (pintype "passive"))
      (node (ref "R11") (pin "2") (pinfunction "2_2") (pintype "passive"))
    )
    (net (code "85") (name "Net-(VCC*1-VCC)") (class "Default")
      (node (ref "C19") (pin "1") (pinfunction "1_1") (pintype "passive"))
      (node (ref "C21") (pin "2") (pinfunction "2_2") (pintype "passive"))
      (node (ref "F2") (pin "2") (pinfunction "2_2") (pintype "passive"))
      (node (ref "VCC*1") (pin "1") (pinfunction "VCC_1") (pintype "passive"))
    )
    (net (code "86") (name "Net-(VCC*2-VCC)") (class "Default")
      (node (ref "C26") (pin "1") (pinfunction "1_1") (pintype "passive"))
      (node (ref "C28") (pin "2") (pinfunction "2_2") (pintype "passive"))
      (node (ref "F1") (pin "1") (pinfunction "1_1") (pintype "passive"))
      (node (ref "VCC*2") (pin "1") (pinfunction "VCC_1") (pintype "passive"))
    )
    (net (code "87") (name "Net-(Y1-VDD)") (class "Default")
      (node (ref "C24") (pin "2") (pinfunction "2_2") (pintype "passive"))
      (node (ref "C25") (pin "2") (pinfunction "2_2") (pintype "passive"))
      (node (ref "L3") (pin "2") (pinfunction "2_2") (pintype "passive"))
      (node (ref "Y1") (pin "4") (pinfunction "VDD_4") (pintype "passive"))
    )
    (net (code "88") (name "VCC") (class "Default")
      (node (ref "F2") (pin "1") (pinfunction "1_1") (pintype "passive"))
      (node (ref "P6") (pin "1") (pinfunction "1_1") (pintype "passive"))
      (node (ref "P6") (pin "2") (pinfunction "2_2") (pintype "passive"))
      (node (ref "P6") (pin "3") (pinfunction "3_3") (pintype "passive"))
      (node (ref "P6") (pin "4") (pinfunction "4_4") (pintype "passive"))
    )
    (net (code "89") (name "unconnected-(MCU*1-ADC0_DM1-Pad15)") (class "Default")
      (node (ref "MCU*1") (pin "15") (pinfunction "ADC0_DM1_15") (pintype "passive"))
    )
    (net (code "90") (name "unconnected-(MCU*1-ADC0_DP1-Pad14)") (class "Default")
      (node (ref "MCU*1") (pin "14") (pinfunction "ADC0_DP1_14") (pintype "passive"))
    )
    (net (code "91") (name "unconnected-(MCU*1-ADC1_DM1-Pad17)") (class "Default")
      (node (ref "MCU*1") (pin "17") (pinfunction "ADC1_DM1_17") (pintype "passive"))
    )
    (net (code "92") (name "unconnected-(MCU*1-ADC1_DP1-Pad16)") (class "Default")
      (node (ref "MCU*1") (pin "16") (pinfunction "ADC1_DP1_16") (pintype "passive"))
    )
    (net (code "93") (name "unconnected-(MCU*1-DAC0_OUT-Pad27)") (class "Default")
      (node (ref "MCU*1") (pin "27") (pinfunction "DAC0_OUT_27") (pintype "passive"))
    )
    (net (code "94") (name "unconnected-(MCU*1-EXTAL32-Pad29)") (class "Default")
      (node (ref "MCU*1") (pin "29") (pinfunction "EXTAL32_29") (pintype "passive"))
    )
    (net (code "95") (name "unconnected-(MCU*1-PGA0_DM{slash}ADC0_DM0{slash}ADC1_DM3-Pad19)") (class "Default")
      (node (ref "MCU*1") (pin "19") (pinfunction "PGA0_DM/ADC0_DM0/ADC1_DM3_19") (pintype "passive"))
    )
    (net (code "96") (name "unconnected-(MCU*1-PGA0_DP{slash}ADC0_DP0{slash}ADC1_DP3-Pad18)") (class "Default")
      (node (ref "MCU*1") (pin "18") (pinfunction "PGA0_DP/ADC0_DP0/ADC1_DP3_18") (pintype "passive"))
    )
    (net (code "97") (name "unconnected-(MCU*1-PGA1_DM{slash}ADC1_DM0{slash}ADC0_DM3-Pad21)") (class "Default")
      (node (ref "MCU*1") (pin "21") (pinfunction "PGA1_DM/ADC1_DM0/ADC0_DM3_21") (pintype "passive"))
    )
    (net (code "98") (name "unconnected-(MCU*1-PGA1_DP{slash}ADC1_DP0{slash}ADC0_DP3-Pad20)") (class "Default")
      (node (ref "MCU*1") (pin "20") (pinfunction "PGA1_DP/ADC1_DP0/ADC0_DP3_20") (pintype "passive"))
    )
    (net (code "99") (name "unconnected-(MCU*1-VREF_OUT{slash}CMP1_IN5CMP0_IN5{slash}ADC1_SE18-Pad26)") (class "Default")
      (node (ref "MCU*1") (pin "26") (pinfunction "VREF_OUT/CMP1_IN5CMP0_IN5/ADC1_SE18_26") (pintype "passive"))
    )
    (net (code "100") (name "unconnected-(MCU*1-XTAL32-Pad28)") (class "Default")
      (node (ref "MCU*1") (pin "28") (pinfunction "XTAL32_28") (pintype "passive"))
    )
    (net (code "101") (name "unconnected-(P8-Pad5)") (class "Default")
      (node (ref "P8") (pin "5") (pinfunction "5_5") (pintype "passive+no_connect"))
    )
    (net (code "102") (name "unconnected-(P8-Pad6)") (class "Default")
      (node (ref "P8") (pin "6") (pinfunction "6_6") (pintype "passive+no_connect"))
    )
    (net (code "103") (name "unconnected-(Y1-NC-Pad1)") (class "Default")
      (node (ref "Y1") (pin "1") (pinfunction "NC_1") (pintype "passive+no_connect"))
    )
  )
)
